# Reciever_Schematic.net
KiCad netlist of a schematic drawn in EAGLE
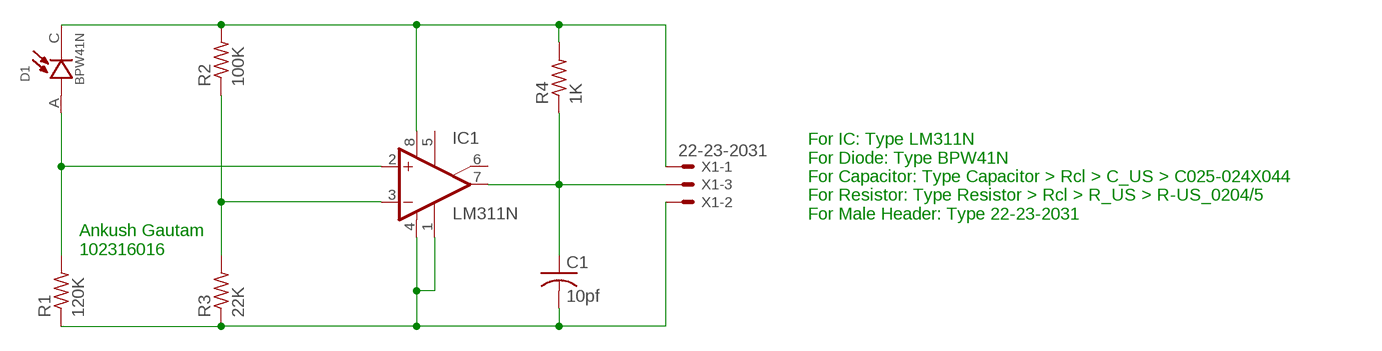
[diagram p0: schematic, sheet 1]

(export (version "E")
  (design (tool "Eeschema 10.0.6"))
  (components
    (comp (ref "C1")
      (value "10pf")
      (footprint "eagle-import:C025-025X050")
      (libsource (lib "eagle-import") (part "C-US025-025X050"))
    )
    (comp (ref "D1")
      (value "BPW41N")
      (footprint "eagle-import:DIO_BPW41N")
      (fields (field (name "MF") "Vishay Semiconductor Opto Division"))
      (libsource (lib "eagle-import") (part "BPW41N"))
    )
    (comp (ref "IC1")
      (value "LM311N")
      (footprint "eagle-import:DIL08")
      (libsource (lib "eagle-import") (part "LM311N"))
    )
    (comp (ref "R1")
      (value "120K")
      (footprint "eagle-import:0204_5")
      (libsource (lib "eagle-import") (part "R-US_0204/5"))
    )
    (comp (ref "R2")
      (value "100K")
      (footprint "eagle-import:0204_5")
      (libsource (lib "eagle-import") (part "R-US_0204/5"))
    )
    (comp (ref "R3")
      (value "22K")
      (footprint "eagle-import:0204_5")
      (libsource (lib "eagle-import") (part "R-US_0204/5"))
    )
    (comp (ref "R4")
      (value "1K")
      (footprint "eagle-import:0204_5")
      (libsource (lib "eagle-import") (part "R-US_0204/5"))
    )
    (comp (ref "X1")
      (value "22-23-2031")
      (footprint "eagle-import:22-23-2031")
      (fields (field (name "MF") "MOLEX"))
      (libsource (lib "eagle-import") (part "22-23-2031"))
    )
  )
  (nets
    (net (code "1") (name "Net-(IC1-+IN)") (class "Default")
      (node (ref "D1") (pin "A") (pinfunction "A_A") (pintype "passive"))
      (node (ref "IC1") (pin "2") (pinfunction "+IN_2") (pintype "input"))
      (node (ref "R1") (pin "2") (pinfunction "2_2") (pintype "passive"))
    )
    (net (code "2") (name "Net-(IC1--IN)") (class "Default")
      (node (ref "IC1") (pin "3") (pinfunction "-IN_3") (pintype "input"))
      (node (ref "R2") (pin "1") (pinfunction "1_1") (pintype "passive"))
      (node (ref "R3") (pin "2") (pinfunction "2_2") (pintype "passive"))
    )
    (net (code "3") (name "Net-(IC1-GND)") (class "Default")
      (node (ref "C1") (pin "2") (pinfunction "2_2") (pintype "passive"))
      (node (ref "IC1") (pin "1") (pinfunction "GND_1") (pintype "passive"))
      (node (ref "IC1") (pin "4") (pinfunction "V-_4") (pintype "power_in"))
      (node (ref "R1") (pin "1") (pinfunction "1_1") (pintype "passive"))
      (node (ref "R3") (pin "1") (pinfunction "1_1") (pintype "passive"))
      (node (ref "X1") (pin "2") (pinfunction "S_2") (pintype "passive"))
    )
    (net (code "4") (name "Net-(IC1-OUT)") (class "Default")
      (node (ref "C1") (pin "1") (pinfunction "1_1") (pintype "passive"))
      (node (ref "IC1") (pin "7") (pinfunction "OUT_7") (pintype "output"))
      (node (ref "R4") (pin "1") (pinfunction "1_1") (pintype "passive"))
      (node (ref "X1") (pin "3") (pinfunction "S_3") (pintype "passive"))
    )
    (net (code "5") (name "Net-(IC1-V+)") (class "Default")
      (node (ref "D1") (pin "C") (pinfunction "C_C") (pintype "passive"))
      (node (ref "IC1") (pin "8") (pinfunction "V+_8") (pintype "power_in"))
      (node (ref "R2") (pin "2") (pinfunction "2_2") (pintype "passive"))
      (node (ref "R4") (pin "2") (pinfunction "2_2") (pintype "passive"))
      (node (ref "X1") (pin "1") (pinfunction "S_1") (pintype "passive"))
    )
    (net (code "6") (name "unconnected-(IC1-ON-Pad5)") (class "Default")
      (node (ref "IC1") (pin "5") (pinfunction "ON_5") (pintype "passive"))
    )
    (net (code "7") (name "unconnected-(IC1-ON{slash}STR-Pad6)") (class "Default")
      (node (ref "IC1") (pin "6") (pinfunction "ON/STR_6") (pintype "passive"))
    )
  )
)
